# RollerShutterNode.net
KiCad netlist of a schematic drawn in EAGLE
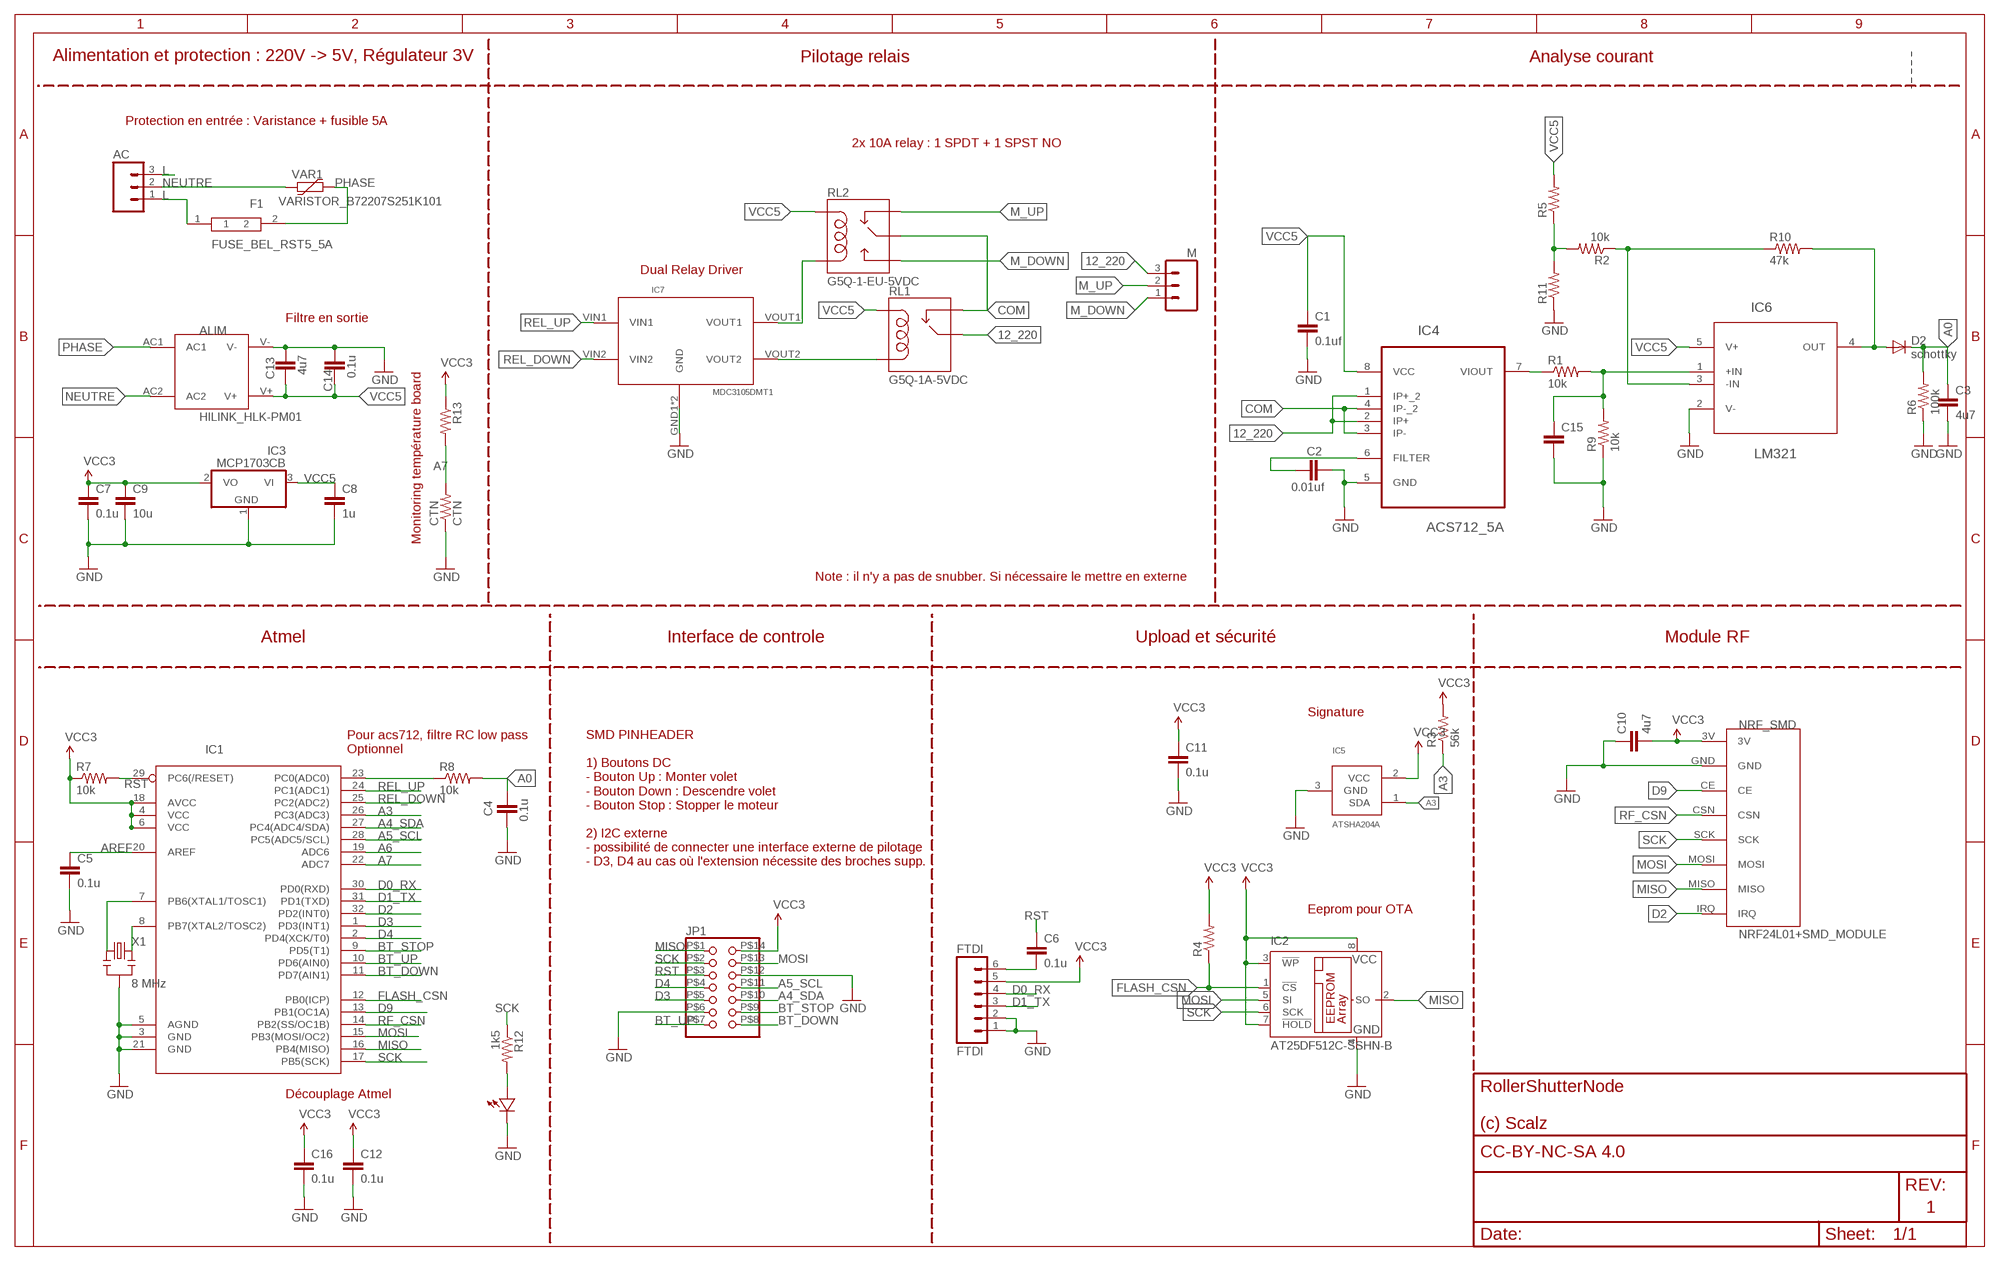
[diagram p0: schematic, sheet 1]

(export (version "E")
  (design (tool "Eeschema 10.0.6"))
  (components
    (comp (ref "AC")
      (value "M03-SCREW-5MM")
      (footprint "eagle-import:SCREWTERMINAL-5MM-3")
      (libsource (lib "eagle-import") (part "M03-SCREW-5MM"))
    )
    (comp (ref "ALIM")
      (value "HILINK_HLK-PM01")
      (footprint "eagle-import:HILINK_HLK-PM01")
      (libsource (lib "eagle-import") (part "HILINK_HLK-PM01"))
    )
    (comp (ref "C1")
      (value "0.1uf")
      (footprint "eagle-import:0805-CAP")
      (libsource (lib "eagle-import") (part "CAP0805-CAP"))
    )
    (comp (ref "C2")
      (value "0.01uf")
      (footprint "eagle-import:0805-CAP")
      (libsource (lib "eagle-import") (part "CAP0805-CAP"))
    )
    (comp (ref "C3")
      (value "4u7")
      (footprint "eagle-import:0805-CAP")
      (libsource (lib "eagle-import") (part "CAP0805-CAP"))
    )
    (comp (ref "C4")
      (value "0.1u")
      (footprint "eagle-import:0805-CAP")
      (libsource (lib "eagle-import") (part "CAP0805-CAP"))
    )
    (comp (ref "C5")
      (value "0.1u")
      (footprint "eagle-import:0805-CAP")
      (libsource (lib "eagle-import") (part "CAP0805-CAP"))
    )
    (comp (ref "C6")
      (value "0.1u")
      (footprint "eagle-import:0805-CAP")
      (libsource (lib "eagle-import") (part "CAP0805-CAP"))
    )
    (comp (ref "C7")
      (value "0.1u")
      (footprint "eagle-import:0805-CAP")
      (libsource (lib "eagle-import") (part "CAP0805-CAP"))
    )
    (comp (ref "C8")
      (value "1u")
      (footprint "eagle-import:0805-CAP")
      (libsource (lib "eagle-import") (part "CAP0805-CAP"))
    )
    (comp (ref "C9")
      (value "10u")
      (footprint "eagle-import:0805-CAP")
      (libsource (lib "eagle-import") (part "CAP0805-CAP"))
    )
    (comp (ref "C10")
      (value "4u7")
      (footprint "eagle-import:0805-CAP")
      (libsource (lib "eagle-import") (part "CAP0805-CAP"))
    )
    (comp (ref "C11")
      (value "0.1u")
      (footprint "eagle-import:0805-CAP")
      (libsource (lib "eagle-import") (part "CAP0805-CAP"))
    )
    (comp (ref "C12")
      (value "0.1u")
      (footprint "eagle-import:0805-CAP")
      (libsource (lib "eagle-import") (part "CAP0805-CAP"))
    )
    (comp (ref "C13")
      (value "4u7")
      (footprint "eagle-import:0805-CAP")
      (libsource (lib "eagle-import") (part "CAP0805-CAP"))
    )
    (comp (ref "C14")
      (value "0.1u")
      (footprint "eagle-import:0805-CAP")
      (libsource (lib "eagle-import") (part "CAP0805-CAP"))
    )
    (comp (ref "C15")
      (value "CAP0805-CAP")
      (footprint "eagle-import:0805-CAP")
      (libsource (lib "eagle-import") (part "CAP0805-CAP"))
    )
    (comp (ref "C16")
      (value "0.1u")
      (footprint "eagle-import:0805-CAP")
      (libsource (lib "eagle-import") (part "CAP0805-CAP"))
    )
    (comp (ref "CTN")
      (value "CTN")
      (footprint "eagle-import:0805-RES")
      (libsource (lib "eagle-import") (part "RESISTOR0805-RES"))
    )
    (comp (ref "D1")
      (value "LED0805")
      (footprint "eagle-import:0805-LED")
      (libsource (lib "eagle-import") (part "LED0805"))
    )
    (comp (ref "D2")
      (value "schottky")
      (footprint "eagle-import:SOD-323")
      (libsource (lib "eagle-import") (part "DIODESOD"))
    )
    (comp (ref "F1")
      (value "FUSE_BEL_RST5_5A")
      (footprint "eagle-import:FUSE_BEL_RST5_5A")
      (libsource (lib "eagle-import") (part "FUSE_BEL_RST5_5A"))
    )
    (comp (ref "FTDI")
      (value "FTDI")
      (footprint "eagle-import:1X06")
      (libsource (lib "eagle-import") (part "M06SIP"))
    )
    (comp (ref "IC1")
      (value "ATMega-328")
      (footprint "eagle-import:TQFP32-08")
      (libsource (lib "eagle-import") (part "ATMEGA168/328TQFP32"))
    )
    (comp (ref "IC2")
      (value "AT25DF512C-SSHN-B")
      (footprint "eagle-import:SO-08")
      (fields (field (name "MF") "MICROCHIP") (field (name "MPN") "25AA080/SN"))
      (libsource (lib "eagle-import") (part "25SNAA080"))
    )
    (comp (ref "IC3")
      (value "MCP1703CB")
      (footprint "eagle-import:SOT23")
      (libsource (lib "eagle-import") (part "MCP1703CB"))
    )
    (comp (ref "IC4")
      (value "ACS712_5A")
      (footprint "eagle-import:SOIC127P600X175-8N")
      (fields (field (name "MPN") "ACS712ELCTR-20A-T"))
      (libsource (lib "eagle-import") (part "ACS712ELCTR-20A-T"))
    )
    (comp (ref "IC5")
      (value "ATSHA204A")
      (footprint "eagle-import:SOT23")
      (libsource (lib "eagle-import") (part "ATSHA204A"))
    )
    (comp (ref "IC6")
      (value "LM321")
      (footprint "eagle-import:SOT95P285X120-5N")
      (fields (field (name "MPN") "LM321MF"))
      (libsource (lib "eagle-import") (part "LM321MF"))
    )
    (comp (ref "IC7")
      (value "MDC3105DMT1")
      (footprint "eagle-import:MDC3105DMT1")
      (libsource (lib "eagle-import") (part "MDC3105DMT1"))
    )
    (comp (ref "JP1")
      (value "PINHD-2X7")
      (footprint "eagle-import:2X07")
      (libsource (lib "eagle-import") (part "PINHD-2X7"))
    )
    (comp (ref "M")
      (value "M03-SCREW-5MM")
      (footprint "eagle-import:SCREWTERMINAL-5MM-3")
      (libsource (lib "eagle-import") (part "M03-SCREW-5MM"))
    )
    (comp (ref "NRF_SMD")
      (value "NRF24L01+SMD_MODULE")
      (footprint "eagle-import:NRF24L01+SMD_MODULE")
      (libsource (lib "eagle-import") (part "NRF24L01+SMD_MODULE"))
    )
    (comp (ref "R1")
      (value "10k")
      (footprint "eagle-import:0805-RES")
      (libsource (lib "eagle-import") (part "RESISTOR0805-RES"))
    )
    (comp (ref "R2")
      (value "10k")
      (footprint "eagle-import:0805-RES")
      (libsource (lib "eagle-import") (part "RESISTOR0805-RES"))
    )
    (comp (ref "R3")
      (value "56k")
      (footprint "eagle-import:0805-RES")
      (libsource (lib "eagle-import") (part "RESISTOR0805-RES"))
    )
    (comp (ref "R4")
      (value "RESISTOR0805-RES")
      (footprint "eagle-import:0805-RES")
      (libsource (lib "eagle-import") (part "RESISTOR0805-RES"))
    )
    (comp (ref "R5")
      (value "RESISTOR0805-RES")
      (footprint "eagle-import:0805-RES")
      (libsource (lib "eagle-import") (part "RESISTOR0805-RES"))
    )
    (comp (ref "R6")
      (value "100k")
      (footprint "eagle-import:0805-RES")
      (libsource (lib "eagle-import") (part "RESISTOR0805-RES"))
    )
    (comp (ref "R7")
      (value "10k")
      (footprint "eagle-import:0805-RES")
      (libsource (lib "eagle-import") (part "RESISTOR0805-RES"))
    )
    (comp (ref "R8")
      (value "10k")
      (footprint "eagle-import:0805-RES")
      (libsource (lib "eagle-import") (part "RESISTOR0805-RES"))
    )
    (comp (ref "R9")
      (value "10k")
      (footprint "eagle-import:0805-RES")
      (libsource (lib "eagle-import") (part "RESISTOR0805-RES"))
    )
    (comp (ref "R10")
      (value "47k")
      (footprint "eagle-import:0805-RES")
      (libsource (lib "eagle-import") (part "RESISTOR0805-RES"))
    )
    (comp (ref "R11")
      (value "RESISTOR0805-RES")
      (footprint "eagle-import:0805-RES")
      (libsource (lib "eagle-import") (part "RESISTOR0805-RES"))
    )
    (comp (ref "R12")
      (value "1k5")
      (footprint "eagle-import:0805-RES")
      (libsource (lib "eagle-import") (part "RESISTOR0805-RES"))
    )
    (comp (ref "R13")
      (value "RESISTOR0805-RES")
      (footprint "eagle-import:0805-RES")
      (libsource (lib "eagle-import") (part "RESISTOR0805-RES"))
    )
    (comp (ref "RL1")
      (value "G5Q-1A-5VDC")
      (footprint "eagle-import:G5Q_SINGLE")
      (libsource (lib "eagle-import") (part "G5Q_SINGLE"))
    )
    (comp (ref "RL2")
      (value "G5Q-1-EU-5VDC")
      (footprint "eagle-import:RELAY-G5Q")
      (libsource (lib "eagle-import") (part "RELAYPTH"))
    )
    (comp (ref "VAR1")
      (value "VARISTOR_B72207S251K101")
      (footprint "eagle-import:VARISTOR_B72207S251K101")
      (libsource (lib "eagle-import") (part "VARISTOR_B72207S251K101"))
    )
    (comp (ref "X1")
      (value "8 MHz")
      (footprint "eagle-import:RESONATOR-SMD")
      (libsource (lib "eagle-import") (part "RESONATORSMD"))
    )
  )
  (nets
    (net (code "1") (name "/A4_SDA") (class "Default")
      (node (ref "IC1") (pin "27") (pinfunction "PC4(ADC4/SDA)_27") (pintype "bidirectional"))
      (node (ref "JP1") (pin "P$10") (pinfunction "10_P$10") (pintype "passive"))
    )
    (net (code "2") (name "/A5_SCL") (class "Default")
      (node (ref "IC1") (pin "28") (pinfunction "PC5(ADC5/SCL)_28") (pintype "bidirectional"))
      (node (ref "JP1") (pin "P$11") (pinfunction "8_P$11") (pintype "passive"))
    )
    (net (code "3") (name "/A6") (class "Default")
      (node (ref "IC1") (pin "19") (pinfunction "ADC6_19") (pintype "bidirectional"))
    )
    (net (code "4") (name "/A7") (class "Default")
      (node (ref "CTN") (pin "2") (pinfunction "2_2") (pintype "passive"))
      (node (ref "IC1") (pin "22") (pinfunction "ADC7_22") (pintype "bidirectional"))
      (node (ref "R13") (pin "2") (pinfunction "2_2") (pintype "passive"))
    )
    (net (code "5") (name "/AREF") (class "Default")
      (node (ref "C5") (pin "1") (pinfunction "1_1") (pintype "passive"))
      (node (ref "IC1") (pin "20") (pinfunction "AREF_20") (pintype "bidirectional"))
    )
    (net (code "6") (name "/BT_DOWN") (class "Default")
      (node (ref "IC1") (pin "11") (pinfunction "PD7(AIN1)_11") (pintype "bidirectional"))
      (node (ref "JP1") (pin "P$8") (pinfunction "14_P$8") (pintype "passive"))
    )
    (net (code "7") (name "/BT_STOP") (class "Default")
      (node (ref "IC1") (pin "9") (pinfunction "PD5(T1)_9") (pintype "bidirectional"))
      (node (ref "JP1") (pin "P$9") (pinfunction "12_P$9") (pintype "passive"))
    )
    (net (code "8") (name "/BT_UP") (class "Default")
      (node (ref "IC1") (pin "10") (pinfunction "PD6(AIN0)_10") (pintype "bidirectional"))
      (node (ref "JP1") (pin "P$7") (pinfunction "13_P$7") (pintype "passive"))
    )
    (net (code "9") (name "/D0_RX") (class "Default")
      (node (ref "FTDI") (pin "4") (pinfunction "4_4") (pintype "passive"))
      (node (ref "IC1") (pin "30") (pinfunction "PD0(RXD)_30") (pintype "bidirectional"))
    )
    (net (code "10") (name "/D1_TX") (class "Default")
      (node (ref "FTDI") (pin "3") (pinfunction "3_3") (pintype "passive"))
      (node (ref "IC1") (pin "31") (pinfunction "PD1(TXD)_31") (pintype "bidirectional"))
    )
    (net (code "11") (name "/D3") (class "Default")
      (node (ref "IC1") (pin "1") (pinfunction "PD3(INT1)_1") (pintype "bidirectional"))
      (node (ref "JP1") (pin "P$5") (pinfunction "9_P$5") (pintype "passive"))
    )
    (net (code "12") (name "/D4") (class "Default")
      (node (ref "IC1") (pin "2") (pinfunction "PD4(XCK/T0)_2") (pintype "bidirectional"))
      (node (ref "JP1") (pin "P$4") (pinfunction "7_P$4") (pintype "passive"))
    )
    (net (code "13") (name "/L") (class "Default")
      (node (ref "AC") (pin "1") (pinfunction "1_1") (pintype "passive"))
      (node (ref "AC") (pin "3") (pinfunction "3_3") (pintype "passive"))
      (node (ref "F1") (pin "1") (pinfunction "1_1") (pintype "bidirectional"))
    )
    (net (code "14") (name "/RST") (class "Default")
      (node (ref "C6") (pin "1") (pinfunction "1_1") (pintype "passive"))
      (node (ref "IC1") (pin "29") (pinfunction "PC6(/RESET)_29") (pintype "bidirectional"))
      (node (ref "JP1") (pin "P$3") (pinfunction "5_P$3") (pintype "passive"))
      (node (ref "R7") (pin "2") (pinfunction "2_2") (pintype "passive"))
    )
    (net (code "15") (name "12_220") (class "Default")
      (node (ref "IC4") (pin "1") (pinfunction "IP+_2_1") (pintype "input"))
      (node (ref "IC4") (pin "2") (pinfunction "IP+_2") (pintype "input"))
      (node (ref "M") (pin "3") (pinfunction "3_3") (pintype "passive"))
      (node (ref "RL1") (pin "2") (pinfunction "MAIN_2") (pintype "bidirectional"))
    )
    (net (code "16") (name "A0") (class "Default")
      (node (ref "C3") (pin "1") (pinfunction "1_1") (pintype "passive"))
      (node (ref "C4") (pin "2") (pinfunction "2_2") (pintype "passive"))
      (node (ref "D2") (pin "1") (pinfunction "C_1") (pintype "passive"))
      (node (ref "R6") (pin "2") (pinfunction "2_2") (pintype "passive"))
      (node (ref "R8") (pin "2") (pinfunction "2_2") (pintype "passive"))
    )
    (net (code "17") (name "A3") (class "Default")
      (node (ref "IC1") (pin "26") (pinfunction "PC3(ADC3)_26") (pintype "bidirectional"))
      (node (ref "IC5") (pin "1") (pinfunction "SDA_1") (pintype "bidirectional"))
      (node (ref "R3") (pin "1") (pinfunction "1_1") (pintype "passive"))
    )
    (net (code "18") (name "COM") (class "Default")
      (node (ref "IC4") (pin "3") (pinfunction "IP-_3") (pintype "input"))
      (node (ref "IC4") (pin "4") (pinfunction "IP-_2_4") (pintype "input"))
      (node (ref "RL1") (pin "3") (pinfunction "NC_3") (pintype "bidirectional"))
      (node (ref "RL2") (pin "2") (pinfunction "MAIN_2") (pintype "bidirectional"))
    )
    (net (code "19") (name "D2") (class "Default")
      (node (ref "IC1") (pin "32") (pinfunction "PD2(INT0)_32") (pintype "bidirectional"))
      (node (ref "NRF_SMD") (pin "IRQ") (pinfunction "IRQ_IRQ") (pintype "bidirectional"))
    )
    (net (code "20") (name "D9") (class "Default")
      (node (ref "IC1") (pin "13") (pinfunction "PB1(OC1A)_13") (pintype "bidirectional"))
      (node (ref "NRF_SMD") (pin "CE") (pinfunction "CE_CE") (pintype "bidirectional"))
    )
    (net (code "21") (name "FLASH_CSN") (class "Default")
      (node (ref "IC1") (pin "12") (pinfunction "PB0(ICP)_12") (pintype "bidirectional"))
      (node (ref "IC2") (pin "1") (pinfunction "~{CS}_1") (pintype "input"))
      (node (ref "R4") (pin "1") (pinfunction "1_1") (pintype "passive"))
    )
    (net (code "22") (name "GND") (class "Default")
      (node (ref "ALIM") (pin "V-") (pinfunction "V-_V-") (pintype "bidirectional"))
      (node (ref "C1") (pin "2") (pinfunction "2_2") (pintype "passive"))
      (node (ref "C10") (pin "1") (pinfunction "1_1") (pintype "passive"))
      (node (ref "C11") (pin "2") (pinfunction "2_2") (pintype "passive"))
      (node (ref "C12") (pin "2") (pinfunction "2_2") (pintype "passive"))
      (node (ref "C13") (pin "2") (pinfunction "2_2") (pintype "passive"))
      (node (ref "C14") (pin "2") (pinfunction "2_2") (pintype "passive"))
      (node (ref "C15") (pin "2") (pinfunction "2_2") (pintype "passive"))
      (node (ref "C16") (pin "2") (pinfunction "2_2") (pintype "passive"))
      (node (ref "C2") (pin "2") (pinfunction "2_2") (pintype "passive"))
      (node (ref "C3") (pin "2") (pinfunction "2_2") (pintype "passive"))
      (node (ref "C4") (pin "1") (pinfunction "1_1") (pintype "passive"))
      (node (ref "C5") (pin "2") (pinfunction "2_2") (pintype "passive"))
      (node (ref "C7") (pin "2") (pinfunction "2_2") (pintype "passive"))
      (node (ref "C8") (pin "2") (pinfunction "2_2") (pintype "passive"))
      (node (ref "C9") (pin "2") (pinfunction "2_2") (pintype "passive"))
      (node (ref "CTN") (pin "1") (pinfunction "1_1") (pintype "passive"))
      (node (ref "D1") (pin "MINUS") (pinfunction "MINUS_MINUS") (pintype "passive"))
      (node (ref "FTDI") (pin "1") (pinfunction "1_1") (pintype "passive"))
      (node (ref "FTDI") (pin "2") (pinfunction "2_2") (pintype "passive"))
      (node (ref "IC1") (pin "21") (pinfunction "GND_21") (pintype "bidirectional"))
      (node (ref "IC1") (pin "3") (pinfunction "GND_3") (pintype "bidirectional"))
      (node (ref "IC1") (pin "5") (pinfunction "AGND_5") (pintype "bidirectional"))
      (node (ref "IC2") (pin "4") (pinfunction "GND_4") (pintype "power_in"))
      (node (ref "IC3") (pin "1") (pinfunction "GND_1") (pintype "passive"))
      (node (ref "IC4") (pin "5") (pinfunction "GND_5") (pintype "passive"))
      (node (ref "IC5") (pin "3") (pinfunction "GND_3") (pintype "bidirectional"))
      (node (ref "IC6") (pin "2") (pinfunction "V-_2") (pintype "power_in"))
      (node (ref "IC7") (pin "GND1") (pinfunction "GND_GND1") (pintype "bidirectional"))
      (node (ref "IC7") (pin "GND2") (pinfunction "GND_GND2") (pintype "bidirectional"))
      (node (ref "JP1") (pin "P$12") (pinfunction "6_P$12") (pintype "passive"))
      (node (ref "JP1") (pin "P$6") (pinfunction "11_P$6") (pintype "passive"))
      (node (ref "NRF_SMD") (pin "GND") (pinfunction "GND_GND") (pintype "bidirectional"))
      (node (ref "R11") (pin "1") (pinfunction "1_1") (pintype "passive"))
      (node (ref "R6") (pin "1") (pinfunction "1_1") (pintype "passive"))
      (node (ref "R9") (pin "1") (pinfunction "1_1") (pintype "passive"))
      (node (ref "X1") (pin "2") (pinfunction "2_2") (pintype "passive"))
    )
    (net (code "23") (name "MISO") (class "Default")
      (node (ref "IC1") (pin "16") (pinfunction "PB4(MISO)_16") (pintype "bidirectional"))
      (node (ref "IC2") (pin "2") (pinfunction "SO_2") (pintype "bidirectional"))
      (node (ref "JP1") (pin "P$1") (pinfunction "1_P$1") (pintype "passive"))
      (node (ref "NRF_SMD") (pin "MISO") (pinfunction "MISO_MISO") (pintype "bidirectional"))
    )
    (net (code "24") (name "MOSI") (class "Default")
      (node (ref "IC1") (pin "15") (pinfunction "PB3(MOSI/OC2)_15") (pintype "bidirectional"))
      (node (ref "IC2") (pin "5") (pinfunction "SI_5") (pintype "input"))
      (node (ref "JP1") (pin "P$13") (pinfunction "4_P$13") (pintype "passive"))
      (node (ref "NRF_SMD") (pin "MOSI") (pinfunction "MOSI_MOSI") (pintype "bidirectional"))
    )
    (net (code "25") (name "M_DOWN") (class "Default")
      (node (ref "M") (pin "1") (pinfunction "1_1") (pintype "passive"))
      (node (ref "RL2") (pin "3") (pinfunction "NO_3") (pintype "bidirectional"))
    )
    (net (code "26") (name "M_UP") (class "Default")
      (node (ref "M") (pin "2") (pinfunction "2_2") (pintype "passive"))
      (node (ref "RL2") (pin "4") (pinfunction "NC_4") (pintype "bidirectional"))
    )
    (net (code "27") (name "NEUTRE") (class "Default")
      (node (ref "AC") (pin "2") (pinfunction "2_2") (pintype "passive"))
      (node (ref "ALIM") (pin "AC2") (pinfunction "AC2_AC2") (pintype "bidirectional"))
      (node (ref "VAR1") (pin "1") (pinfunction "1_1") (pintype "passive"))
    )
    (net (code "28") (name "Net-(C6-Pad2)") (class "Default")
      (node (ref "C6") (pin "2") (pinfunction "2_2") (pintype "passive"))
      (node (ref "FTDI") (pin "6") (pinfunction "6_6") (pintype "passive"))
    )
    (net (code "29") (name "Net-(D1-PadPLUS)") (class "Default")
      (node (ref "D1") (pin "PLUS") (pinfunction "PLUS_PLUS") (pintype "passive"))
      (node (ref "R12") (pin "2") (pinfunction "2_2") (pintype "passive"))
    )
    (net (code "30") (name "Net-(D2-A)") (class "Default")
      (node (ref "D2") (pin "2") (pinfunction "A_2") (pintype "passive"))
      (node (ref "IC6") (pin "4") (pinfunction "OUT_4") (pintype "output"))
      (node (ref "R10") (pin "2") (pinfunction "2_2") (pintype "passive"))
    )
    (net (code "31") (name "Net-(IC1-PB6(XTAL1{slash}TOSC1))") (class "Default")
      (node (ref "IC1") (pin "7") (pinfunction "PB6(XTAL1/TOSC1)_7") (pintype "bidirectional"))
      (node (ref "X1") (pin "1") (pinfunction "1_1") (pintype "passive"))
    )
    (net (code "32") (name "Net-(IC1-PB7(XTAL2{slash}TOSC2))") (class "Default")
      (node (ref "IC1") (pin "8") (pinfunction "PB7(XTAL2/TOSC2)_8") (pintype "bidirectional"))
      (node (ref "X1") (pin "3") (pinfunction "3_3") (pintype "passive"))
    )
    (net (code "33") (name "Net-(IC1-PC0(ADC0))") (class "Default")
      (node (ref "IC1") (pin "23") (pinfunction "PC0(ADC0)_23") (pintype "bidirectional"))
      (node (ref "R8") (pin "1") (pinfunction "1_1") (pintype "passive"))
    )
    (net (code "34") (name "Net-(IC4-FILTER)") (class "Default")
      (node (ref "C2") (pin "1") (pinfunction "1_1") (pintype "passive"))
      (node (ref "IC4") (pin "6") (pinfunction "FILTER_6") (pintype "input"))
    )
    (net (code "35") (name "Net-(IC4-VIOUT)") (class "Default")
      (node (ref "IC4") (pin "7") (pinfunction "VIOUT_7") (pintype "output"))
      (node (ref "R1") (pin "1") (pinfunction "1_1") (pintype "passive"))
    )
    (net (code "36") (name "Net-(IC6-+IN)") (class "Default")
      (node (ref "C15") (pin "1") (pinfunction "1_1") (pintype "passive"))
      (node (ref "IC6") (pin "1") (pinfunction "+IN_1") (pintype "input"))
      (node (ref "R1") (pin "2") (pinfunction "2_2") (pintype "passive"))
      (node (ref "R9") (pin "2") (pinfunction "2_2") (pintype "passive"))
    )
    (net (code "37") (name "Net-(IC6--IN)") (class "Default")
      (node (ref "IC6") (pin "3") (pinfunction "-IN_3") (pintype "input"))
      (node (ref "R10") (pin "1") (pinfunction "1_1") (pintype "passive"))
      (node (ref "R2") (pin "1") (pinfunction "1_1") (pintype "passive"))
    )
    (net (code "38") (name "Net-(R11-Pad2)") (class "Default")
      (node (ref "R11") (pin "2") (pinfunction "2_2") (pintype "passive"))
      (node (ref "R2") (pin "2") (pinfunction "2_2") (pintype "passive"))
      (node (ref "R5") (pin "1") (pinfunction "1_1") (pintype "passive"))
    )
    (net (code "39") (name "Net-(RL1-COIL2)") (class "Default")
      (node (ref "IC7") (pin "VOUT2") (pinfunction "VOUT2_VOUT2") (pintype "bidirectional"))
      (node (ref "RL1") (pin "5") (pinfunction "COIL2_5") (pintype "bidirectional"))
    )
    (net (code "40") (name "Net-(RL2-COIL2)") (class "Default")
      (node (ref "IC7") (pin "VOUT1") (pinfunction "VOUT1_VOUT1") (pintype "bidirectional"))
      (node (ref "RL2") (pin "1") (pinfunction "COIL2_1") (pintype "bidirectional"))
    )
    (net (code "41") (name "PHASE") (class "Default")
      (node (ref "ALIM") (pin "AC1") (pinfunction "AC1_AC1") (pintype "bidirectional"))
      (node (ref "F1") (pin "2") (pinfunction "2_2") (pintype "bidirectional"))
      (node (ref "VAR1") (pin "2") (pinfunction "2_2") (pintype "passive"))
    )
    (net (code "42") (name "REL_DOWN") (class "Default")
      (node (ref "IC1") (pin "25") (pinfunction "PC2(ADC2)_25") (pintype "bidirectional"))
      (node (ref "IC7") (pin "VIN2") (pinfunction "VIN2_VIN2") (pintype "bidirectional"))
    )
    (net (code "43") (name "REL_UP") (class "Default")
      (node (ref "IC1") (pin "24") (pinfunction "PC1(ADC1)_24") (pintype "bidirectional"))
      (node (ref "IC7") (pin "VIN1") (pinfunction "VIN1_VIN1") (pintype "bidirectional"))
    )
    (net (code "44") (name "RF_CSN") (class "Default")
      (node (ref "IC1") (pin "14") (pinfunction "PB2(SS/OC1B)_14") (pintype "bidirectional"))
      (node (ref "NRF_SMD") (pin "CSN") (pinfunction "CSN_CSN") (pintype "bidirectional"))
    )
    (net (code "45") (name "SCK") (class "Default")
      (node (ref "IC1") (pin "17") (pinfunction "PB5(SCK)_17") (pintype "bidirectional"))
      (node (ref "IC2") (pin "6") (pinfunction "SCK_6") (pintype "input"))
      (node (ref "JP1") (pin "P$2") (pinfunction "3_P$2") (pintype "passive"))
      (node (ref "NRF_SMD") (pin "SCK") (pinfunction "SCK_SCK") (pintype "bidirectional"))
      (node (ref "R12") (pin "1") (pinfunction "1_1") (pintype "passive"))
    )
    (net (code "46") (name "VCC3") (class "Default")
      (node (ref "C10") (pin "2") (pinfunction "2_2") (pintype "passive"))
      (node (ref "C11") (pin "1") (pinfunction "1_1") (pintype "passive"))
      (node (ref "C12") (pin "1") (pinfunction "1_1") (pintype "passive"))
      (node (ref "C16") (pin "1") (pinfunction "1_1") (pintype "passive"))
      (node (ref "C7") (pin "1") (pinfunction "1_1") (pintype "passive"))
      (node (ref "C9") (pin "1") (pinfunction "1_1") (pintype "passive"))
      (node (ref "FTDI") (pin "5") (pinfunction "5_5") (pintype "passive"))
      (node (ref "IC1") (pin "18") (pinfunction "AVCC_18") (pintype "bidirectional"))
      (node (ref "IC1") (pin "4") (pinfunction "VCC_4") (pintype "bidirectional"))
      (node (ref "IC1") (pin "6") (pinfunction "VCC_6") (pintype "bidirectional"))
      (node (ref "IC2") (pin "3") (pinfunction "~{WP}_3") (pintype "input"))
      (node (ref "IC2") (pin "7") (pinfunction "~{HOLD}_7") (pintype "input"))
      (node (ref "IC2") (pin "8") (pinfunction "VCC_8") (pintype "power_in"))
      (node (ref "IC3") (pin "2") (pinfunction "VO_2") (pintype "passive"))
      (node (ref "IC5") (pin "2") (pinfunction "VCC_2") (pintype "bidirectional"))
      (node (ref "JP1") (pin "P$14") (pinfunction "2_P$14") (pintype "passive"))
      (node (ref "NRF_SMD") (pin "3V") (pinfunction "3V_3V") (pintype "bidirectional"))
      (node (ref "R13") (pin "1") (pinfunction "1_1") (pintype "passive"))
      (node (ref "R3") (pin "2") (pinfunction "2_2") (pintype "passive"))
      (node (ref "R4") (pin "2") (pinfunction "2_2") (pintype "passive"))
      (node (ref "R7") (pin "1") (pinfunction "1_1") (pintype "passive"))
    )
    (net (code "47") (name "VCC5") (class "Default")
      (node (ref "ALIM") (pin "V+") (pinfunction "V+_V+") (pintype "bidirectional"))
      (node (ref "C1") (pin "1") (pinfunction "1_1") (pintype "passive"))
      (node (ref "C13") (pin "1") (pinfunction "1_1") (pintype "passive"))
      (node (ref "C14") (pin "1") (pinfunction "1_1") (pintype "passive"))
      (node (ref "C8") (pin "1") (pinfunction "1_1") (pintype "passive"))
      (node (ref "IC3") (pin "3") (pinfunction "VI_3") (pintype "input"))
      (node (ref "IC4") (pin "8") (pinfunction "VCC_8") (pintype "power_in"))
      (node (ref "IC6") (pin "5") (pinfunction "V+_5") (pintype "power_in"))
      (node (ref "R5") (pin "2") (pinfunction "2_2") (pintype "passive"))
      (node (ref "RL1") (pin "1") (pinfunction "COIL1_1") (pintype "bidirectional"))
      (node (ref "RL2") (pin "5") (pinfunction "COIL1_5") (pintype "bidirectional"))
    )
  )
)
